# uklad_pomiaru_pradu.net
KiCad netlist of a schematic drawn in Altium Designer
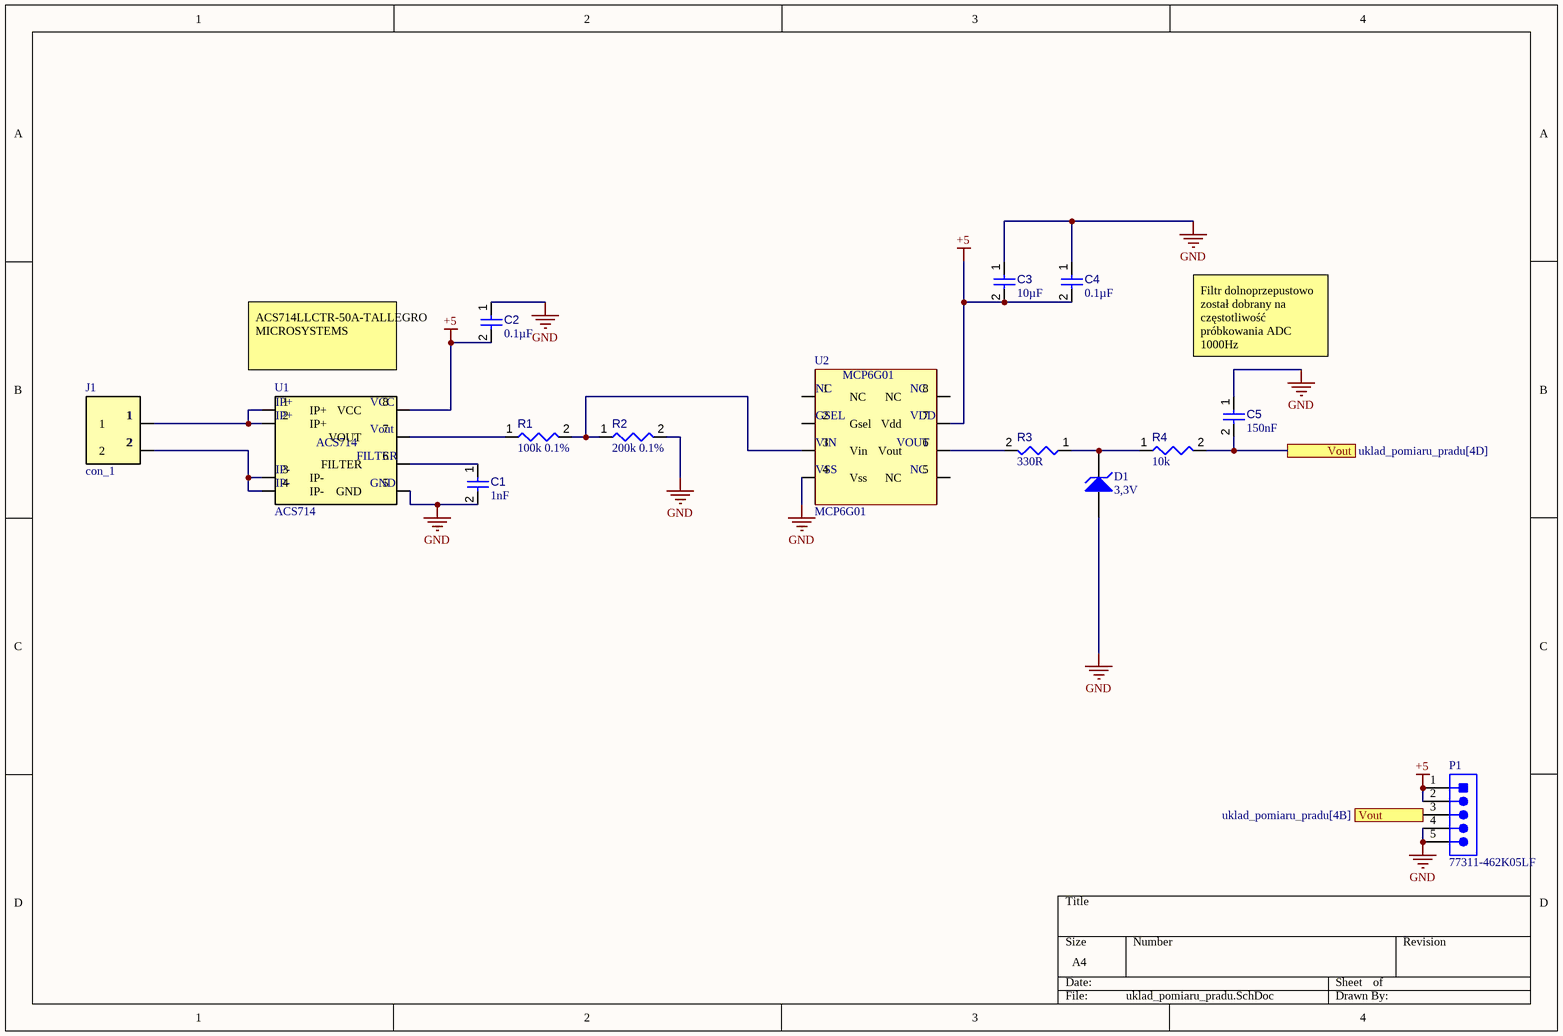
[diagram p0: uklad_pomiaru_pradu.SchDoc]

(export (version "E")
  (design (tool "Eeschema 10.0.6"))
  (components
    (comp (ref "C1")
      (value "1nF")
      (footprint "CAPC2013X145X50ML20T25")
      (description "Chip Capacitor, 1 uF, +/-10%, 25 V, 0805 (2012 Metric)")
      (fields (field (name "TOLERANCE") "10%") (field (name "Comment") "Capacitor 1 uF +/- 10% 25 V 0805"))
      (libsource (lib "Bartłomiej Raczyński") (part "CAP-NP-2"))
    )
    (comp (ref "C2")
      (value "0.1µF")
      (footprint "CAPC2013X145X50ML20T25")
      (description "Chip Capacitor, 1 uF, +/-10%, 25 V, 0805 (2012 Metric)")
      (fields (field (name "TOLERANCE") "10%") (field (name "Comment") "Capacitor 1 uF +/- 10% 25 V 0805"))
      (libsource (lib "Bartłomiej Raczyński") (part "CAP-NP-2"))
    )
    (comp (ref "C3")
      (value "10µF")
      (footprint "CAPC2013X145X50ML20T25")
      (description "Chip Capacitor, 1 uF, +/-10%, 25 V, 0805 (2012 Metric)")
      (fields (field (name "TOLERANCE") "10%") (field (name "Comment") "Capacitor 1 uF +/- 10% 25 V 0805"))
      (libsource (lib "Bartłomiej Raczyński") (part "CAP-NP-2"))
    )
    (comp (ref "C4")
      (value "0.1µF")
      (footprint "CAPC2013X145X50ML20T25")
      (description "Chip Capacitor, 1 uF, +/-10%, 25 V, 0805 (2012 Metric)")
      (fields (field (name "TOLERANCE") "10%") (field (name "Comment") "Capacitor 1 uF +/- 10% 25 V 0805"))
      (libsource (lib "Bartłomiej Raczyński") (part "CAP-NP-2"))
    )
    (comp (ref "C5")
      (value "150nF")
      (footprint "CAPC2013X145X50ML20T25")
      (description "Chip Capacitor, 1 uF, +/-10%, 25 V, 0805 (2012 Metric)")
      (fields (field (name "TOLERANCE") "10%") (field (name "Comment") "Capacitor 1 uF +/- 10% 25 V 0805"))
      (libsource (lib "Bartłomiej Raczyński") (part "CAP-NP-2"))
    )
    (comp (ref "D1")
      (value "3,3V")
      (footprint "FAIR-DO-35-2")
      (description "Zener Diode, 3.6 V, 5 mA, -65 to 200 degC, 2-Pin DO-35, RoHS, Bulk")
      (fields (field (name "MANUFACTURER") "Fairchild Semiconductor") (field (name "TOLERANCE") "6%"))
      (libsource (lib "Bartłomiej Raczyński") (part "DZEN-AK-2"))
    )
    (comp (ref "J1") (value "con_1") (footprint "con_1") (libsource (lib "zad_space") (part "con_1")))
    (comp (ref "P1")
      (value "77311-462K05LF")
      (footprint "FCI-77311-5_V")
      (fields (field (name "MANUFACTURER") "FCI Electronics"))
      (libsource (lib "Bartłomiej Raczyński") (part "CN-1P-M-R5"))
    )
    (comp (ref "R1")
      (value "100k 0.1%")
      (footprint "RESC3216X60X45ML15T20")
      (description "Chip Resistor, 100 KOhm, +/- 1%, 0.25 W, -55 to 155 degC, 1206 (3216 Metric)")
      (fields (field (name "TOLERANCE") "1%") (field (name "POWER") "250mW"))
      (libsource (lib "Bartłomiej Raczyński") (part "RES-2"))
    )
    (comp (ref "R2")
      (value "200k 0.1%")
      (footprint "RESC3216X60X45ML15T20")
      (description "Chip Resistor, 100 KOhm, +/- 1%, 0.25 W, -55 to 155 degC, 1206 (3216 Metric)")
      (fields (field (name "TOLERANCE") "1%") (field (name "POWER") "250mW"))
      (libsource (lib "Bartłomiej Raczyński") (part "RES-2"))
    )
    (comp (ref "R3")
      (value "330R")
      (footprint "RESC3216X60X45ML15T20")
      (description "Chip Resistor, 100 KOhm, +/- 1%, 0.25 W, -55 to 155 degC, 1206 (3216 Metric)")
      (fields (field (name "TOLERANCE") "1%") (field (name "POWER") "250mW"))
      (libsource (lib "Bartłomiej Raczyński") (part "RES-2"))
    )
    (comp (ref "R4")
      (value "10k")
      (footprint "RESC3216X60X45ML15T20")
      (description "Chip Resistor, 100 KOhm, +/- 1%, 0.25 W, -55 to 155 degC, 1206 (3216 Metric)")
      (fields (field (name "TOLERANCE") "1%") (field (name "POWER") "250mW"))
      (libsource (lib "Bartłomiej Raczyński") (part "RES-2"))
    )
    (comp (ref "U1")
      (value "ACS714")
      (footprint "SOIC127P600X175-8N")
      (libsource (lib "zad_space") (part "ACS714"))
    )
    (comp (ref "U2")
      (value "MCP6G01")
      (footprint "SOIC127P600X175-8N")
      (libsource (lib "zad_space") (part "MCP6G01"))
    )
  )
  (nets
    (net (code "1") (name "+5") (class "Default")
      (node (ref "C2") (pin "2") (pinfunction "2_2") (pintype "passive"))
      (node (ref "C3") (pin "2") (pinfunction "2_2") (pintype "passive"))
      (node (ref "C4") (pin "2") (pinfunction "2_2") (pintype "passive"))
      (node (ref "P1") (pin "1") (pinfunction "DTR_1") (pintype "passive"))
      (node (ref "P1") (pin "2") (pinfunction "RXI_2") (pintype "passive"))
      (node (ref "U1") (pin "8") (pinfunction "VCC_8") (pintype "passive"))
      (node (ref "U2") (pin "7") (pinfunction "Vdd_7") (pintype "passive"))
    )
    (net (code "2") (name "/Vout") (class "Default")
      (node (ref "C5") (pin "2") (pinfunction "2_2") (pintype "passive"))
      (node (ref "P1") (pin "3") (pinfunction "TXO_3") (pintype "passive"))
      (node (ref "R4") (pin "2") (pinfunction "2_2") (pintype "passive"))
    )
    (net (code "3") (name "GND") (class "Default")
      (node (ref "C1") (pin "2") (pinfunction "2_2") (pintype "passive"))
      (node (ref "C2") (pin "1") (pinfunction "1_1") (pintype "passive"))
      (node (ref "C3") (pin "1") (pinfunction "1_1") (pintype "passive"))
      (node (ref "C4") (pin "1") (pinfunction "1_1") (pintype "passive"))
      (node (ref "C5") (pin "1") (pinfunction "1_1") (pintype "passive"))
      (node (ref "D1") (pin "1") (pinfunction "A_1") (pintype "passive"))
      (node (ref "P1") (pin "4") (pinfunction "VCC_4") (pintype "passive"))
      (node (ref "P1") (pin "5") (pinfunction "CTS_5") (pintype "passive"))
      (node (ref "R2") (pin "2") (pinfunction "2_2") (pintype "passive"))
      (node (ref "U1") (pin "5") (pinfunction "GND_5") (pintype "passive"))
      (node (ref "U2") (pin "4") (pinfunction "Vss_4") (pintype "passive"))
    )
    (net (code "4") (name "Net-(D1-K)") (class "Default")
      (node (ref "D1") (pin "2") (pinfunction "K_2") (pintype "passive"))
      (node (ref "R3") (pin "1") (pinfunction "1_1") (pintype "passive"))
      (node (ref "R4") (pin "1") (pinfunction "1_1") (pintype "passive"))
    )
    (net (code "5") (name "Net-(J1-Pad1)") (class "Default")
      (node (ref "J1") (pin "1") (pinfunction "1_1") (pintype "passive"))
      (node (ref "U1") (pin "1") (pinfunction "IP+_1") (pintype "passive"))
      (node (ref "U1") (pin "2") (pinfunction "IP+_2") (pintype "passive"))
    )
    (net (code "6") (name "Net-(J1-Pad2)") (class "Default")
      (node (ref "J1") (pin "2") (pinfunction "2_2") (pintype "passive"))
      (node (ref "U1") (pin "3") (pinfunction "IP-_3") (pintype "passive"))
      (node (ref "U1") (pin "4") (pinfunction "IP-_4") (pintype "passive"))
    )
    (net (code "7") (name "Net-(U1-FILTER)") (class "Default")
      (node (ref "C1") (pin "1") (pinfunction "1_1") (pintype "passive"))
      (node (ref "U1") (pin "6") (pinfunction "FILTER_6") (pintype "passive"))
    )
    (net (code "8") (name "Net-(U1-VOUT)") (class "Default")
      (node (ref "R1") (pin "1") (pinfunction "1_1") (pintype "passive"))
      (node (ref "U1") (pin "7") (pinfunction "VOUT_7") (pintype "passive"))
    )
    (net (code "9") (name "Net-(U2-Vin)") (class "Default")
      (node (ref "R1") (pin "2") (pinfunction "2_2") (pintype "passive"))
      (node (ref "R2") (pin "1") (pinfunction "1_1") (pintype "passive"))
      (node (ref "U2") (pin "3") (pinfunction "Vin_3") (pintype "passive"))
    )
    (net (code "10") (name "Net-(U2-Vout)") (class "Default")
      (node (ref "R3") (pin "2") (pinfunction "2_2") (pintype "passive"))
      (node (ref "U2") (pin "6") (pinfunction "Vout_6") (pintype "passive"))
    )
    (net (code "11") (name "unconnected-(U2-Gsel-Pad2)") (class "Default")
      (node (ref "U2") (pin "2") (pinfunction "Gsel_2") (pintype "passive"))
    )
    (net (code "12") (name "unconnected-(U2-NC-Pad1)") (class "Default")
      (node (ref "U2") (pin "1") (pinfunction "NC_1") (pintype "passive"))
    )
    (net (code "13") (name "unconnected-(U2-NC-Pad5)") (class "Default")
      (node (ref "U2") (pin "5") (pinfunction "NC_5") (pintype "passive"))
    )
    (net (code "14") (name "unconnected-(U2-NC-Pad8)") (class "Default")
      (node (ref "U2") (pin "8") (pinfunction "NC_8") (pintype "passive"))
    )
  )
)
